# main.net
KiCad netlist of a schematic drawn in EAGLE
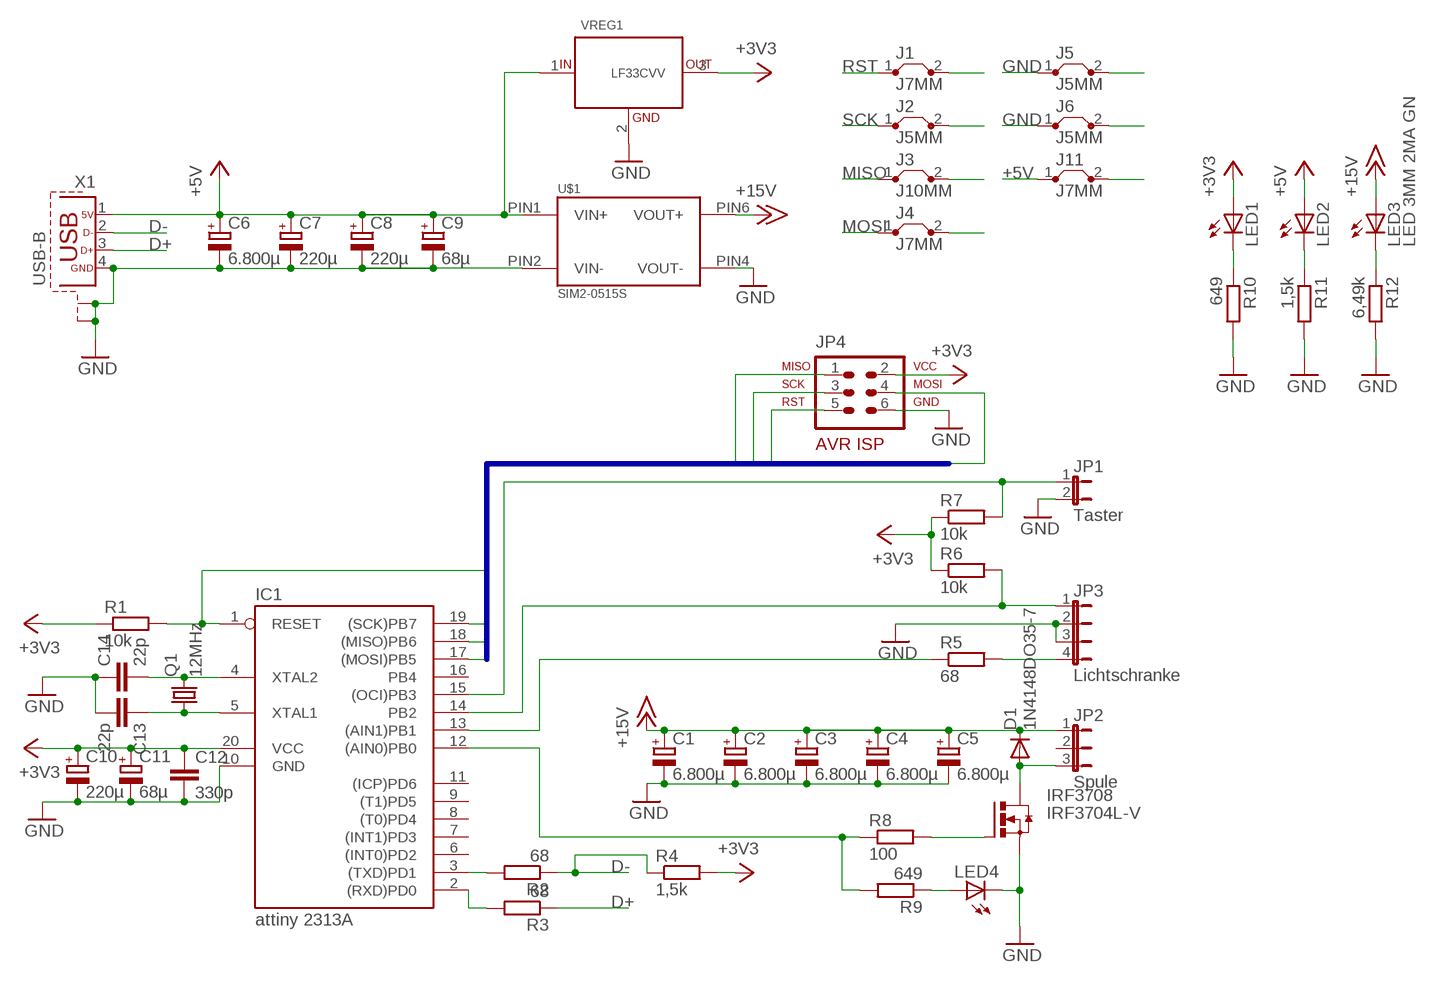
[diagram p0: schematic, sheet 1]

(export (version "E")
  (design (tool "Eeschema 10.0.6"))
  (components
    (comp (ref "C1")
      (value "6.800µ")
      (footprint "eagle-import:E7,5-18")
      (libsource (lib "eagle-import") (part "CPOL-EUE7.5-18"))
    )
    (comp (ref "C2")
      (value "6.800µ")
      (footprint "eagle-import:E7,5-18")
      (libsource (lib "eagle-import") (part "CPOL-EUE7.5-18"))
    )
    (comp (ref "C3")
      (value "6.800µ")
      (footprint "eagle-import:E7,5-18")
      (libsource (lib "eagle-import") (part "CPOL-EUE7.5-18"))
    )
    (comp (ref "C4")
      (value "6.800µ")
      (footprint "eagle-import:E7,5-18")
      (libsource (lib "eagle-import") (part "CPOL-EUE7.5-18"))
    )
    (comp (ref "C5")
      (value "6.800µ")
      (footprint "eagle-import:E7,5-18")
      (libsource (lib "eagle-import") (part "CPOL-EUE7.5-18"))
    )
    (comp (ref "C6")
      (value "6.800µ")
      (footprint "eagle-import:E7,5-18")
      (libsource (lib "eagle-import") (part "CPOL-EUE7.5-18"))
    )
    (comp (ref "C7")
      (value "220µ")
      (footprint "eagle-import:E2,5-7")
      (libsource (lib "eagle-import") (part "CPOL-EUE2.5-7"))
    )
    (comp (ref "C8")
      (value "220µ")
      (footprint "eagle-import:E2,5-7")
      (libsource (lib "eagle-import") (part "CPOL-EUE2.5-7"))
    )
    (comp (ref "C9")
      (value "68µ")
      (footprint "eagle-import:E2,5-7")
      (libsource (lib "eagle-import") (part "CPOL-EUE2.5-7"))
    )
    (comp (ref "C10")
      (value "220µ")
      (footprint "eagle-import:E2,5-7")
      (libsource (lib "eagle-import") (part "CPOL-EUE2.5-7"))
    )
    (comp (ref "C11")
      (value "68µ")
      (footprint "eagle-import:E2,5-7")
      (libsource (lib "eagle-import") (part "CPOL-EUE2.5-7"))
    )
    (comp (ref "C12")
      (value "330p")
      (footprint "eagle-import:C050-024X044")
      (libsource (lib "eagle-import") (part "C-EU050-024X044"))
    )
    (comp (ref "C13")
      (value "22p")
      (footprint "eagle-import:C050-024X044")
      (libsource (lib "eagle-import") (part "C-EU050-024X044"))
    )
    (comp (ref "C14")
      (value "22p")
      (footprint "eagle-import:C050-024X044")
      (libsource (lib "eagle-import") (part "C-EU050-024X044"))
    )
    (comp (ref "D1")
      (value "1N4148DO35-7")
      (footprint "eagle-import:DO35-7")
      (libsource (lib "eagle-import") (part "1N4148DO35-7"))
    )
    (comp (ref "IC1")
      (value "attiny 2313A")
      (footprint "eagle-import:DIL20")
      (libsource (lib "eagle-import") (part "AT90S2313P"))
    )
    (comp (ref "IRF3708")
      (value "IRF3704L-V")
      (footprint "eagle-import:TO262-V")
      (libsource (lib "eagle-import") (part "IRF3704L-V"))
    )
    (comp (ref "J1")
      (value "J7MM")
      (footprint "eagle-import:07")
      (libsource (lib "eagle-import") (part "J7MM"))
    )
    (comp (ref "J2")
      (value "J5MM")
      (footprint "eagle-import:05")
      (libsource (lib "eagle-import") (part "J5MM"))
    )
    (comp (ref "J3")
      (value "J10MM")
      (footprint "eagle-import:10")
      (libsource (lib "eagle-import") (part "J10MM"))
    )
    (comp (ref "J4")
      (value "J7MM")
      (footprint "eagle-import:07")
      (libsource (lib "eagle-import") (part "J7MM"))
    )
    (comp (ref "J5")
      (value "J5MM")
      (footprint "eagle-import:05")
      (libsource (lib "eagle-import") (part "J5MM"))
    )
    (comp (ref "J6")
      (value "J5MM")
      (footprint "eagle-import:05")
      (libsource (lib "eagle-import") (part "J5MM"))
    )
    (comp (ref "J11")
      (value "J7MM")
      (footprint "eagle-import:07")
      (libsource (lib "eagle-import") (part "J7MM"))
    )
    (comp (ref "JP1")
      (value "Taster")
      (footprint "eagle-import:JP1")
      (libsource (lib "eagle-import") (part "JP1E"))
    )
    (comp (ref "JP2")
      (value "Spule")
      (footprint "eagle-import:JP2")
      (libsource (lib "eagle-import") (part "JP2E"))
    )
    (comp (ref "JP3")
      (value "Lichtschranke")
      (footprint "eagle-import:JP4")
      (libsource (lib "eagle-import") (part "JP4E"))
    )
    (comp (ref "JP4")
      (value "AVR-ISP-6VERT")
      (footprint "eagle-import:AVR-ISP-6")
      (libsource (lib "eagle-import") (part "AVR-ISP-6VERT"))
    )
    (comp (ref "LED1")
      (value "LED3MM")
      (footprint "eagle-import:LED3MM")
      (libsource (lib "eagle-import") (part "LED3MM"))
    )
    (comp (ref "LED2")
      (value "LED3MM")
      (footprint "eagle-import:LED3MM")
      (libsource (lib "eagle-import") (part "LED3MM"))
    )
    (comp (ref "LED3")
      (value "LED 3MM 2MA GN")
      (footprint "eagle-import:LED3MM")
      (libsource (lib "eagle-import") (part "LED3MM"))
    )
    (comp (ref "LED4")
      (value "LED3MM")
      (footprint "eagle-import:LED3MM")
      (libsource (lib "eagle-import") (part "LED3MM"))
    )
    (comp (ref "Q1")
      (value "12MHz")
      (footprint "eagle-import:HC18U-V")
      (libsource (lib "eagle-import") (part "CRYSTALHC18U-V"))
    )
    (comp (ref "R1")
      (value "10k")
      (footprint "eagle-import:0207_10")
      (libsource (lib "eagle-import") (part "R-EU_0207/10"))
    )
    (comp (ref "R2")
      (value "68")
      (footprint "eagle-import:0207_10")
      (libsource (lib "eagle-import") (part "R-EU_0207/10"))
    )
    (comp (ref "R3")
      (value "68")
      (footprint "eagle-import:0207_10")
      (libsource (lib "eagle-import") (part "R-EU_0207/10"))
    )
    (comp (ref "R4")
      (value "1,5k")
      (footprint "eagle-import:0207_10")
      (libsource (lib "eagle-import") (part "R-EU_0207/10"))
    )
    (comp (ref "R5")
      (value "68")
      (footprint "eagle-import:0207_10")
      (libsource (lib "eagle-import") (part "R-EU_0207/10"))
    )
    (comp (ref "R6")
      (value "10k")
      (footprint "eagle-import:0207_10")
      (libsource (lib "eagle-import") (part "R-EU_0207/10"))
    )
    (comp (ref "R7")
      (value "10k")
      (footprint "eagle-import:0207_10")
      (libsource (lib "eagle-import") (part "R-EU_0207/10"))
    )
    (comp (ref "R8")
      (value "100")
      (footprint "eagle-import:0207_10")
      (libsource (lib "eagle-import") (part "R-EU_0207/10"))
    )
    (comp (ref "R9")
      (value "649")
      (footprint "eagle-import:0207_10")
      (libsource (lib "eagle-import") (part "R-EU_0207/10"))
    )
    (comp (ref "R10")
      (value "649")
      (footprint "eagle-import:0207_7")
      (libsource (lib "eagle-import") (part "R-EU_0207/7"))
    )
    (comp (ref "R11")
      (value "1,5k")
      (footprint "eagle-import:0207_7")
      (libsource (lib "eagle-import") (part "R-EU_0207/7"))
    )
    (comp (ref "R12")
      (value "6,49k")
      (footprint "eagle-import:0207_10")
      (libsource (lib "eagle-import") (part "R-EU_0207/10"))
    )
    (comp (ref "U$1")
      (value "SIM2-0515S")
      (footprint "eagle-import:SIL7")
      (libsource (lib "eagle-import") (part "SIM2-0515S"))
    )
    (comp (ref "VREG1")
      (value "LF33CVV")
      (footprint "eagle-import:TO220V")
      (libsource (lib "eagle-import") (part "LF33CVV"))
    )
    (comp (ref "X1")
      (value "USB-B")
      (footprint "eagle-import:USB-B")
      (libsource (lib "eagle-import") (part "USB-B"))
    )
  )
  (nets
    (net (code "1") (name "+3V3") (class "Default")
      (node (ref "C10") (pin "+") (pinfunction "+_+") (pintype "passive"))
      (node (ref "C11") (pin "+") (pinfunction "+_+") (pintype "passive"))
      (node (ref "C12") (pin "1") (pinfunction "1_1") (pintype "passive"))
      (node (ref "IC1") (pin "20") (pinfunction "VCC_20") (pintype "power_in"))
      (node (ref "JP4") (pin "2") (pinfunction "2_2") (pintype "passive"))
      (node (ref "LED1") (pin "A") (pinfunction "A_A") (pintype "passive"))
      (node (ref "R1") (pin "1") (pinfunction "1_1") (pintype "passive"))
      (node (ref "R4") (pin "2") (pinfunction "2_2") (pintype "passive"))
      (node (ref "R6") (pin "1") (pinfunction "1_1") (pintype "passive"))
      (node (ref "R7") (pin "1") (pinfunction "1_1") (pintype "passive"))
      (node (ref "VREG1") (pin "3") (pinfunction "OUT_3") (pintype "output"))
    )
    (net (code "2") (name "+5V") (class "Default")
      (node (ref "C6") (pin "+") (pinfunction "+_+") (pintype "passive"))
      (node (ref "C7") (pin "+") (pinfunction "+_+") (pintype "passive"))
      (node (ref "C8") (pin "+") (pinfunction "+_+") (pintype "passive"))
      (node (ref "C9") (pin "+") (pinfunction "+_+") (pintype "passive"))
      (node (ref "J11") (pin "1") (pinfunction "1_1") (pintype "passive"))
      (node (ref "J11") (pin "2") (pinfunction "2_2") (pintype "passive"))
      (node (ref "LED2") (pin "A") (pinfunction "A_A") (pintype "passive"))
      (node (ref "U$1") (pin "PIN1") (pinfunction "VIN+_PIN1") (pintype "power_in"))
      (node (ref "VREG1") (pin "1") (pinfunction "IN_1") (pintype "input"))
      (node (ref "X1") (pin "1") (pinfunction "1_1") (pintype "passive"))
    )
    (net (code "3") (name "+15V") (class "Default")
      (node (ref "C1") (pin "+") (pinfunction "+_+") (pintype "passive"))
      (node (ref "C2") (pin "+") (pinfunction "+_+") (pintype "passive"))
      (node (ref "C3") (pin "+") (pinfunction "+_+") (pintype "passive"))
      (node (ref "C4") (pin "+") (pinfunction "+_+") (pintype "passive"))
      (node (ref "C5") (pin "+") (pinfunction "+_+") (pintype "passive"))
      (node (ref "D1") (pin "C") (pinfunction "C_C") (pintype "passive"))
      (node (ref "JP2") (pin "1") (pinfunction "1_1") (pintype "passive"))
      (node (ref "LED3") (pin "A") (pinfunction "A_A") (pintype "passive"))
      (node (ref "U$1") (pin "PIN6") (pinfunction "VOUT+_PIN6") (pintype "power_in"))
    )
    (net (code "4") (name "/D+") (class "Default")
      (node (ref "R3") (pin "1") (pinfunction "1_1") (pintype "passive"))
      (node (ref "X1") (pin "3") (pinfunction "3_3") (pintype "passive"))
    )
    (net (code "5") (name "/D-") (class "Default")
      (node (ref "R2") (pin "1") (pinfunction "1_1") (pintype "passive"))
      (node (ref "R4") (pin "1") (pinfunction "1_1") (pintype "passive"))
      (node (ref "X1") (pin "2") (pinfunction "2_2") (pintype "passive"))
    )
    (net (code "6") (name "/MISO") (class "Default")
      (node (ref "IC1") (pin "18") (pinfunction "(MISO)PB6_18") (pintype "bidirectional"))
      (node (ref "J3") (pin "1") (pinfunction "1_1") (pintype "passive"))
      (node (ref "J3") (pin "2") (pinfunction "2_2") (pintype "passive"))
      (node (ref "JP4") (pin "1") (pinfunction "1_1") (pintype "passive"))
    )
    (net (code "7") (name "/MOSI") (class "Default")
      (node (ref "IC1") (pin "17") (pinfunction "(MOSI)PB5_17") (pintype "bidirectional"))
      (node (ref "J4") (pin "1") (pinfunction "1_1") (pintype "passive"))
      (node (ref "J4") (pin "2") (pinfunction "2_2") (pintype "passive"))
      (node (ref "JP4") (pin "4") (pinfunction "4_4") (pintype "passive"))
    )
    (net (code "8") (name "/RST") (class "Default")
      (node (ref "IC1") (pin "1") (pinfunction "RESET_1") (pintype "bidirectional"))
      (node (ref "J1") (pin "1") (pinfunction "1_1") (pintype "passive"))
      (node (ref "J1") (pin "2") (pinfunction "2_2") (pintype "passive"))
      (node (ref "JP4") (pin "5") (pinfunction "5_5") (pintype "passive"))
      (node (ref "R1") (pin "2") (pinfunction "2_2") (pintype "passive"))
    )
    (net (code "9") (name "/SCK") (class "Default")
      (node (ref "IC1") (pin "19") (pinfunction "(SCK)PB7_19") (pintype "bidirectional"))
      (node (ref "J2") (pin "1") (pinfunction "1_1") (pintype "passive"))
      (node (ref "J2") (pin "2") (pinfunction "2_2") (pintype "passive"))
      (node (ref "JP4") (pin "3") (pinfunction "3_3") (pintype "passive"))
    )
    (net (code "10") (name "GND") (class "Default")
      (node (ref "C1") (pin "-") (pinfunction "-_-") (pintype "passive"))
      (node (ref "C10") (pin "-") (pinfunction "-_-") (pintype "passive"))
      (node (ref "C11") (pin "-") (pinfunction "-_-") (pintype "passive"))
      (node (ref "C12") (pin "2") (pinfunction "2_2") (pintype "passive"))
      (node (ref "C13") (pin "2") (pinfunction "2_2") (pintype "passive"))
      (node (ref "C14") (pin "1") (pinfunction "1_1") (pintype "passive"))
      (node (ref "C2") (pin "-") (pinfunction "-_-") (pintype "passive"))
      (node (ref "C3") (pin "-") (pinfunction "-_-") (pintype "passive"))
      (node (ref "C4") (pin "-") (pinfunction "-_-") (pintype "passive"))
      (node (ref "C5") (pin "-") (pinfunction "-_-") (pintype "passive"))
      (node (ref "C6") (pin "-") (pinfunction "-_-") (pintype "passive"))
      (node (ref "C7") (pin "-") (pinfunction "-_-") (pintype "passive"))
      (node (ref "C8") (pin "-") (pinfunction "-_-") (pintype "passive"))
      (node (ref "C9") (pin "-") (pinfunction "-_-") (pintype "passive"))
      (node (ref "IC1") (pin "10") (pinfunction "GND_10") (pintype "power_in"))
      (node (ref "IRF3708") (pin "3") (pinfunction "S_3") (pintype "passive"))
      (node (ref "J5") (pin "1") (pinfunction "1_1") (pintype "passive"))
      (node (ref "J5") (pin "2") (pinfunction "2_2") (pintype "passive"))
      (node (ref "J6") (pin "1") (pinfunction "1_1") (pintype "passive"))
      (node (ref "J6") (pin "2") (pinfunction "2_2") (pintype "passive"))
      (node (ref "JP1") (pin "2") (pinfunction "2_2") (pintype "passive"))
      (node (ref "JP3") (pin "2") (pinfunction "2_2") (pintype "passive"))
      (node (ref "JP3") (pin "3") (pinfunction "3_3") (pintype "passive"))
      (node (ref "JP4") (pin "6") (pinfunction "6_6") (pintype "passive"))
      (node (ref "LED4") (pin "K") (pinfunction "C_K") (pintype "passive"))
      (node (ref "R10") (pin "2") (pinfunction "2_2") (pintype "passive"))
      (node (ref "R11") (pin "2") (pinfunction "2_2") (pintype "passive"))
      (node (ref "R12") (pin "2") (pinfunction "2_2") (pintype "passive"))
      (node (ref "U$1") (pin "PIN2") (pinfunction "VIN-_PIN2") (pintype "power_in"))
      (node (ref "U$1") (pin "PIN4") (pinfunction "VOUT-_PIN4") (pintype "power_in"))
      (node (ref "VREG1") (pin "2") (pinfunction "GND_2") (pintype "input"))
      (node (ref "X1") (pin "4") (pinfunction "4_4") (pintype "passive"))
      (node (ref "X1") (pin "S1") (pinfunction "S1_S1") (pintype "passive"))
      (node (ref "X1") (pin "S2") (pinfunction "S2_S2") (pintype "passive"))
    )
    (net (code "11") (name "Net-(IC1-(AIN0)PB0)") (class "Default")
      (node (ref "IC1") (pin "12") (pinfunction "(AIN0)PB0_12") (pintype "bidirectional"))
      (node (ref "R8") (pin "1") (pinfunction "1_1") (pintype "passive"))
      (node (ref "R9") (pin "2") (pinfunction "2_2") (pintype "passive"))
    )
    (net (code "12") (name "Net-(IC1-(AIN1)PB1)") (class "Default")
      (node (ref "IC1") (pin "13") (pinfunction "(AIN1)PB1_13") (pintype "bidirectional"))
      (node (ref "R5") (pin "1") (pinfunction "1_1") (pintype "passive"))
    )
    (net (code "13") (name "Net-(IC1-(OCI)PB3)") (class "Default")
      (node (ref "IC1") (pin "15") (pinfunction "(OCI)PB3_15") (pintype "bidirectional"))
      (node (ref "JP1") (pin "1") (pinfunction "1_1") (pintype "passive"))
      (node (ref "R7") (pin "2") (pinfunction "2_2") (pintype "passive"))
    )
    (net (code "14") (name "Net-(IC1-(RXD)PD0)") (class "Default")
      (node (ref "IC1") (pin "2") (pinfunction "(RXD)PD0_2") (pintype "bidirectional"))
      (node (ref "R3") (pin "2") (pinfunction "2_2") (pintype "passive"))
    )
    (net (code "15") (name "Net-(IC1-(TXD)PD1)") (class "Default")
      (node (ref "IC1") (pin "3") (pinfunction "(TXD)PD1_3") (pintype "bidirectional"))
      (node (ref "R2") (pin "2") (pinfunction "2_2") (pintype "passive"))
    )
    (net (code "16") (name "Net-(IC1-PB2)") (class "Default")
      (node (ref "IC1") (pin "14") (pinfunction "PB2_14") (pintype "bidirectional"))
      (node (ref "JP3") (pin "1") (pinfunction "1_1") (pintype "passive"))
      (node (ref "R6") (pin "2") (pinfunction "2_2") (pintype "passive"))
    )
    (net (code "17") (name "Net-(IC1-XTAL1)") (class "Default")
      (node (ref "C13") (pin "1") (pinfunction "1_1") (pintype "passive"))
      (node (ref "IC1") (pin "5") (pinfunction "XTAL1_5") (pintype "bidirectional"))
      (node (ref "Q1") (pin "1") (pinfunction "1_1") (pintype "passive"))
    )
    (net (code "18") (name "Net-(IC1-XTAL2)") (class "Default")
      (node (ref "C14") (pin "2") (pinfunction "2_2") (pintype "passive"))
      (node (ref "IC1") (pin "4") (pinfunction "XTAL2_4") (pintype "bidirectional"))
      (node (ref "Q1") (pin "2") (pinfunction "2_2") (pintype "passive"))
    )
    (net (code "19") (name "Net-(IRF3708-D)") (class "Default")
      (node (ref "D1") (pin "A") (pinfunction "A_A") (pintype "passive"))
      (node (ref "IRF3708") (pin "2") (pinfunction "D_2") (pintype "passive"))
      (node (ref "JP2") (pin "3") (pinfunction "3_3") (pintype "passive"))
    )
    (net (code "20") (name "Net-(IRF3708-G)") (class "Default")
      (node (ref "IRF3708") (pin "1") (pinfunction "G_1") (pintype "passive"))
      (node (ref "R8") (pin "2") (pinfunction "2_2") (pintype "passive"))
    )
    (net (code "21") (name "Net-(JP3-Pad4)") (class "Default")
      (node (ref "JP3") (pin "4") (pinfunction "4_4") (pintype "passive"))
      (node (ref "R5") (pin "2") (pinfunction "2_2") (pintype "passive"))
    )
    (net (code "22") (name "Net-(LED1-C)") (class "Default")
      (node (ref "LED1") (pin "K") (pinfunction "C_K") (pintype "passive"))
      (node (ref "R10") (pin "1") (pinfunction "1_1") (pintype "passive"))
    )
    (net (code "23") (name "Net-(LED2-C)") (class "Default")
      (node (ref "LED2") (pin "K") (pinfunction "C_K") (pintype "passive"))
      (node (ref "R11") (pin "1") (pinfunction "1_1") (pintype "passive"))
    )
    (net (code "24") (name "Net-(LED3-C)") (class "Default")
      (node (ref "LED3") (pin "K") (pinfunction "C_K") (pintype "passive"))
      (node (ref "R12") (pin "1") (pinfunction "1_1") (pintype "passive"))
    )
    (net (code "25") (name "Net-(LED4-PadA)") (class "Default")
      (node (ref "LED4") (pin "A") (pinfunction "A_A") (pintype "passive"))
      (node (ref "R9") (pin "1") (pinfunction "1_1") (pintype "passive"))
    )
    (net (code "26") (name "unconnected-(IC1-(ICP)PD6-Pad11)") (class "Default")
      (node (ref "IC1") (pin "11") (pinfunction "(ICP)PD6_11") (pintype "bidirectional"))
    )
    (net (code "27") (name "unconnected-(IC1-(INT0)PD2-Pad6)") (class "Default")
      (node (ref "IC1") (pin "6") (pinfunction "(INT0)PD2_6") (pintype "bidirectional"))
    )
    (net (code "28") (name "unconnected-(IC1-(INT1)PD3-Pad7)") (class "Default")
      (node (ref "IC1") (pin "7") (pinfunction "(INT1)PD3_7") (pintype "bidirectional"))
    )
    (net (code "29") (name "unconnected-(IC1-(T0)PD4-Pad8)") (class "Default")
      (node (ref "IC1") (pin "8") (pinfunction "(T0)PD4_8") (pintype "bidirectional"))
    )
    (net (code "30") (name "unconnected-(IC1-(T1)PD5-Pad9)") (class "Default")
      (node (ref "IC1") (pin "9") (pinfunction "(T1)PD5_9") (pintype "bidirectional"))
    )
    (net (code "31") (name "unconnected-(IC1-PB4-Pad16)") (class "Default")
      (node (ref "IC1") (pin "16") (pinfunction "PB4_16") (pintype "bidirectional"))
    )
    (net (code "32") (name "unconnected-(JP2-Pad2)") (class "Default")
      (node (ref "JP2") (pin "2") (pinfunction "2_2") (pintype "passive"))
    )
  )
)
